# LED.net
KiCad netlist of a schematic drawn in Altium Designer
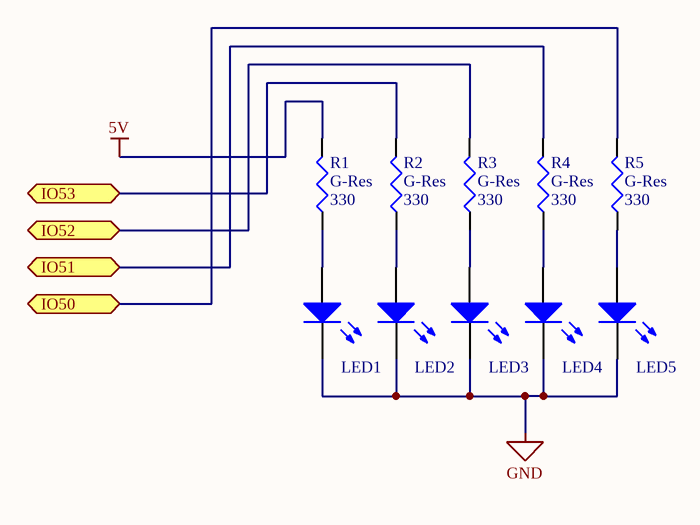
[diagram p0: LED.SchDoc]

(export (version "E")
  (design (tool "Eeschema 10.0.6"))
  (components
    (comp (ref "LED1")
      (value "C503B-RAN-CY0B0AA1")
      (footprint "LED_LGE1.0")
      (description "LED (high intensity - red)")
      (libsource (lib "PartsDatabaseV16.1") (part "T-LEDRedHI"))
    )
    (comp (ref "LED2")
      (value "C503B-RAN-CY0B0AA1")
      (footprint "LED_LGE1.0")
      (description "LED (high intensity - red)")
      (libsource (lib "PartsDatabaseV16.1") (part "T-LEDRedHI"))
    )
    (comp (ref "LED3")
      (value "C503B-RAN-CY0B0AA1")
      (footprint "LED_LGE1.0")
      (description "LED (high intensity - red)")
      (libsource (lib "PartsDatabaseV16.1") (part "T-LEDRedHI"))
    )
    (comp (ref "LED4")
      (value "C503B-RAN-CY0B0AA1")
      (footprint "LED_LGE1.0")
      (description "LED (high intensity - red)")
      (libsource (lib "PartsDatabaseV16.1") (part "T-LEDRedHI"))
    )
    (comp (ref "LED5")
      (value "C503B-RAN-CY0B0AA1")
      (footprint "LED_LGE1.0")
      (description "LED (high intensity - red)")
      (libsource (lib "PartsDatabaseV16.1") (part "T-LEDRedHI"))
    )
    (comp (ref "R1")
      (value "G-Res")
      (footprint "Res10mm_LGE1.0")
      (description "Resistor (specify value)")
      (fields (field (name "ALTIUM_VALUE") "330") (field (name "PUBLISHER") "Altium Limited"))
      (libsource (lib "PartsDatabaseV16.1") (part "G-Res"))
    )
    (comp (ref "R2")
      (value "G-Res")
      (footprint "Res10mm_LGE1.0")
      (description "Resistor (specify value)")
      (fields (field (name "ALTIUM_VALUE") "330") (field (name "PUBLISHER") "Altium Limited"))
      (libsource (lib "PartsDatabaseV16.1") (part "G-Res"))
    )
    (comp (ref "R3")
      (value "G-Res")
      (footprint "Res10mm_LGE1.0")
      (description "Resistor (specify value)")
      (fields (field (name "ALTIUM_VALUE") "330") (field (name "PUBLISHER") "Altium Limited"))
      (libsource (lib "PartsDatabaseV16.1") (part "G-Res"))
    )
    (comp (ref "R4")
      (value "G-Res")
      (footprint "Res10mm_LGE1.0")
      (description "Resistor (specify value)")
      (fields (field (name "ALTIUM_VALUE") "330") (field (name "PUBLISHER") "Altium Limited"))
      (libsource (lib "PartsDatabaseV16.1") (part "G-Res"))
    )
    (comp (ref "R5")
      (value "G-Res")
      (footprint "Res10mm_LGE1.0")
      (description "Resistor (specify value)")
      (fields (field (name "ALTIUM_VALUE") "330") (field (name "PUBLISHER") "Altium Limited"))
      (libsource (lib "PartsDatabaseV16.1") (part "G-Res"))
    )
  )
  (nets
    (net (code "1") (name "/IO50") (class "Default")
      (node (ref "R5") (pin "2") (pinfunction "2_2") (pintype "passive"))
    )
    (net (code "2") (name "/IO51") (class "Default")
      (node (ref "R4") (pin "2") (pinfunction "2_2") (pintype "passive"))
    )
    (net (code "3") (name "/IO52") (class "Default")
      (node (ref "R3") (pin "2") (pinfunction "2_2") (pintype "passive"))
    )
    (net (code "4") (name "/IO53") (class "Default")
      (node (ref "R2") (pin "2") (pinfunction "2_2") (pintype "passive"))
    )
    (net (code "5") (name "5V") (class "Default")
      (node (ref "R1") (pin "2") (pinfunction "2_2") (pintype "passive"))
    )
    (net (code "6") (name "GND") (class "Default")
      (node (ref "LED1") (pin "2") (pinfunction "K_2") (pintype "passive"))
      (node (ref "LED2") (pin "2") (pinfunction "K_2") (pintype "passive"))
      (node (ref "LED3") (pin "2") (pinfunction "K_2") (pintype "passive"))
      (node (ref "LED4") (pin "2") (pinfunction "K_2") (pintype "passive"))
      (node (ref "LED5") (pin "2") (pinfunction "K_2") (pintype "passive"))
    )
    (net (code "7") (name "Net-(LED1-A)") (class "Default")
      (node (ref "LED1") (pin "1") (pinfunction "A_1") (pintype "passive"))
      (node (ref "R1") (pin "1") (pinfunction "1_1") (pintype "passive"))
    )
    (net (code "8") (name "Net-(LED2-A)") (class "Default")
      (node (ref "LED2") (pin "1") (pinfunction "A_1") (pintype "passive"))
      (node (ref "R2") (pin "1") (pinfunction "1_1") (pintype "passive"))
    )
    (net (code "9") (name "Net-(LED3-A)") (class "Default")
      (node (ref "LED3") (pin "1") (pinfunction "A_1") (pintype "passive"))
      (node (ref "R3") (pin "1") (pinfunction "1_1") (pintype "passive"))
    )
    (net (code "10") (name "Net-(LED4-A)") (class "Default")
      (node (ref "LED4") (pin "1") (pinfunction "A_1") (pintype "passive"))
      (node (ref "R4") (pin "1") (pinfunction "1_1") (pintype "passive"))
    )
    (net (code "11") (name "Net-(LED5-A)") (class "Default")
      (node (ref "LED5") (pin "1") (pinfunction "A_1") (pintype "passive"))
      (node (ref "R5") (pin "1") (pinfunction "1_1") (pintype "passive"))
    )
  )
)
